# RasPi-BplusHAT.net
KiCad netlist of a schematic drawn in EAGLE
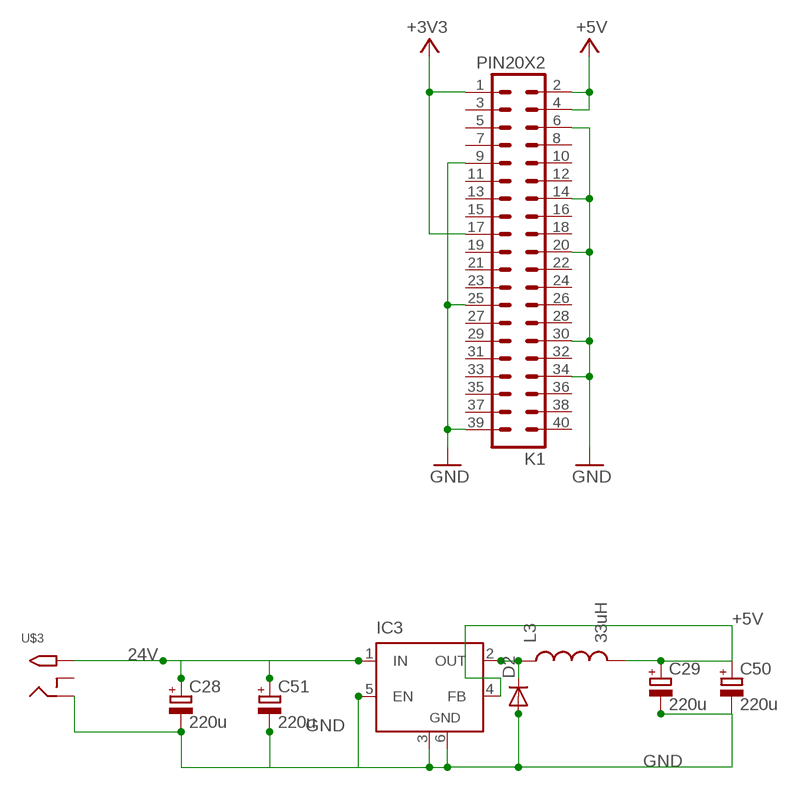
[diagram p0: schematic, sheet 1]
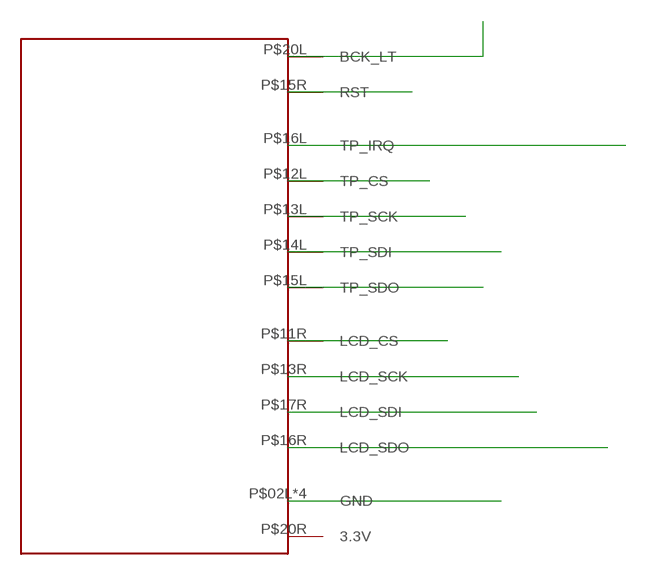
[diagram p1: schematic, sheet 2]

(export (version "E")
  (design (tool "Eeschema 10.0.6"))
  (components
    (comp (ref "C28")
      (value "220u")
      (footprint "eagle-import:E2,5-7")
      (libsource (lib "eagle-import") (part "CPOL-EUE2.5-7"))
    )
    (comp (ref "C29")
      (value "220u")
      (footprint "eagle-import:E2,5-7")
      (libsource (lib "eagle-import") (part "CPOL-EUE2.5-7"))
    )
    (comp (ref "C50")
      (value "220u")
      (footprint "eagle-import:PANASONIC_D")
      (libsource (lib "eagle-import") (part "CPOL-EUD"))
    )
    (comp (ref "C51")
      (value "220u")
      (footprint "eagle-import:PANASONIC_D")
      (libsource (lib "eagle-import") (part "CPOL-EUD"))
    )
    (comp (ref "D2")
      (value "DIODE-DO-214AC")
      (footprint "eagle-import:DO-214AC")
      (libsource (lib "eagle-import") (part "DIODE-DO-214AC"))
    )
    (comp (ref "IC3")
      (value "LM2596S")
      (footprint "eagle-import:TO263-5")
      (libsource (lib "eagle-import") (part "LM2596S"))
    )
    (comp (ref "K1")
      (value "PIN20X2")
      (footprint "eagle-import:PIN_20X2")
      (libsource (lib "eagle-import") (part "PIN20X2"))
    )
    (comp (ref "L3")
      (value "33uH")
      (footprint "eagle-import:CDRH125")
      (libsource (lib "eagle-import") (part "INDUCTORPWR"))
    )
    (comp (ref "U$3")
      (value "2.1MMJACKTHM")
      (footprint "eagle-import:PJ-102A")
      (libsource (lib "eagle-import") (part "2.1MMJACKTHM"))
    )
    (comp (ref "U$1")
      (value "HY28BSTD")
      (footprint "eagle-import:HY28B")
      (libsource (lib "eagle-import") (part "HY28BSTD"))
    )
  )
  (nets
    (net (code "1") (name "+3V3") (class "Default")
      (node (ref "K1") (pin "1") (pinfunction "1_1") (pintype "passive"))
      (node (ref "K1") (pin "17") (pinfunction "17_17") (pintype "passive"))
    )
    (net (code "2") (name "+5V") (class "Default")
      (node (ref "C29") (pin "+") (pinfunction "+_+") (pintype "passive"))
      (node (ref "C50") (pin "+") (pinfunction "+_+") (pintype "passive"))
      (node (ref "IC3") (pin "4") (pinfunction "FB_4") (pintype "input"))
      (node (ref "K1") (pin "2") (pinfunction "2_2") (pintype "passive"))
      (node (ref "K1") (pin "4") (pinfunction "4_4") (pintype "passive"))
      (node (ref "L3") (pin "2") (pinfunction "2_2") (pintype "passive"))
    )
    (net (code "3") (name "24V") (class "Default")
      (node (ref "C28") (pin "+") (pinfunction "+_+") (pintype "passive"))
      (node (ref "C51") (pin "+") (pinfunction "+_+") (pintype "passive"))
      (node (ref "IC3") (pin "1") (pinfunction "IN_1") (pintype "input"))
      (node (ref "U$3") (pin "TIP") (pinfunction "TIP_TIP") (pintype "bidirectional"))
    )
    (net (code "4") (name "GND") (class "Default")
      (node (ref "C28") (pin "-") (pinfunction "-_-") (pintype "passive"))
      (node (ref "C29") (pin "-") (pinfunction "-_-") (pintype "passive"))
      (node (ref "C50") (pin "-") (pinfunction "-_-") (pintype "passive"))
      (node (ref "C51") (pin "-") (pinfunction "-_-") (pintype "passive"))
      (node (ref "D2") (pin "2") (pinfunction "A_2") (pintype "passive"))
      (node (ref "IC3") (pin "3") (pinfunction "GND_3") (pintype "power_in"))
      (node (ref "IC3") (pin "5") (pinfunction "EN_5") (pintype "input"))
      (node (ref "IC3") (pin "6") (pinfunction "GND_6") (pintype "power_in"))
      (node (ref "K1") (pin "14") (pinfunction "14_14") (pintype "passive"))
      (node (ref "K1") (pin "20") (pinfunction "20_20") (pintype "passive"))
      (node (ref "K1") (pin "25") (pinfunction "25_25") (pintype "passive"))
      (node (ref "K1") (pin "30") (pinfunction "30_30") (pintype "passive"))
      (node (ref "K1") (pin "34") (pinfunction "34_34") (pintype "passive"))
      (node (ref "K1") (pin "39") (pinfunction "39_39") (pintype "passive"))
      (node (ref "K1") (pin "6") (pinfunction "6_6") (pintype "passive"))
      (node (ref "K1") (pin "9") (pinfunction "9_9") (pintype "passive"))
      (node (ref "U$3") (pin "RING") (pinfunction "RING_RING") (pintype "bidirectional"))
    )
    (net (code "5") (name "Net-(D2-C)") (class "Default")
      (node (ref "D2") (pin "1") (pinfunction "C_1") (pintype "passive"))
      (node (ref "IC3") (pin "2") (pinfunction "OUT_2") (pintype "output"))
      (node (ref "L3") (pin "1") (pinfunction "1_1") (pintype "passive"))
    )
    (net (code "6") (name "Net-(U$1-GND-PadP$02L)") (class "Default")
      (node (ref "U$1") (pin "P$02L") (pinfunction "GND_P$02L") (pintype "bidirectional"))
      (node (ref "U$1") (pin "P$02R") (pinfunction "GND_P$02R") (pintype "bidirectional"))
      (node (ref "U$1") (pin "P$19L") (pinfunction "GND_P$19L") (pintype "bidirectional"))
      (node (ref "U$1") (pin "P$19R") (pinfunction "GND_P$19R") (pintype "bidirectional"))
    )
    (net (code "7") (name "unconnected-(K1-Pad3)") (class "Default")
      (node (ref "K1") (pin "3") (pinfunction "3_3") (pintype "passive"))
    )
    (net (code "8") (name "unconnected-(K1-Pad5)") (class "Default")
      (node (ref "K1") (pin "5") (pinfunction "5_5") (pintype "passive"))
    )
    (net (code "9") (name "unconnected-(K1-Pad7)") (class "Default")
      (node (ref "K1") (pin "7") (pinfunction "7_7") (pintype "passive"))
    )
    (net (code "10") (name "unconnected-(K1-Pad8)") (class "Default")
      (node (ref "K1") (pin "8") (pinfunction "8_8") (pintype "passive"))
    )
    (net (code "11") (name "unconnected-(K1-Pad10)") (class "Default")
      (node (ref "K1") (pin "10") (pinfunction "10_10") (pintype "passive"))
    )
    (net (code "12") (name "unconnected-(K1-Pad11)") (class "Default")
      (node (ref "K1") (pin "11") (pinfunction "11_11") (pintype "passive"))
    )
    (net (code "13") (name "unconnected-(K1-Pad12)") (class "Default")
      (node (ref "K1") (pin "12") (pinfunction "12_12") (pintype "passive"))
    )
    (net (code "14") (name "unconnected-(K1-Pad13)") (class "Default")
      (node (ref "K1") (pin "13") (pinfunction "13_13") (pintype "passive"))
    )
    (net (code "15") (name "unconnected-(K1-Pad15)") (class "Default")
      (node (ref "K1") (pin "15") (pinfunction "15_15") (pintype "passive"))
    )
    (net (code "16") (name "unconnected-(K1-Pad16)") (class "Default")
      (node (ref "K1") (pin "16") (pinfunction "16_16") (pintype "passive"))
    )
    (net (code "17") (name "unconnected-(K1-Pad18)") (class "Default")
      (node (ref "K1") (pin "18") (pinfunction "18_18") (pintype "passive"))
    )
    (net (code "18") (name "unconnected-(K1-Pad19)") (class "Default")
      (node (ref "K1") (pin "19") (pinfunction "19_19") (pintype "passive"))
    )
    (net (code "19") (name "unconnected-(K1-Pad21)") (class "Default")
      (node (ref "K1") (pin "21") (pinfunction "21_21") (pintype "passive"))
    )
    (net (code "20") (name "unconnected-(K1-Pad22)") (class "Default")
      (node (ref "K1") (pin "22") (pinfunction "22_22") (pintype "passive"))
    )
    (net (code "21") (name "unconnected-(K1-Pad23)") (class "Default")
      (node (ref "K1") (pin "23") (pinfunction "23_23") (pintype "passive"))
    )
    (net (code "22") (name "unconnected-(K1-Pad24)") (class "Default")
      (node (ref "K1") (pin "24") (pinfunction "24_24") (pintype "passive"))
    )
    (net (code "23") (name "unconnected-(K1-Pad26)") (class "Default")
      (node (ref "K1") (pin "26") (pinfunction "26_26") (pintype "passive"))
    )
    (net (code "24") (name "unconnected-(K1-Pad27)") (class "Default")
      (node (ref "K1") (pin "27") (pinfunction "27_27") (pintype "passive"))
    )
    (net (code "25") (name "unconnected-(K1-Pad28)") (class "Default")
      (node (ref "K1") (pin "28") (pinfunction "28_28") (pintype "passive"))
    )
    (net (code "26") (name "unconnected-(K1-Pad29)") (class "Default")
      (node (ref "K1") (pin "29") (pinfunction "29_29") (pintype "passive"))
    )
    (net (code "27") (name "unconnected-(K1-Pad31)") (class "Default")
      (node (ref "K1") (pin "31") (pinfunction "31_31") (pintype "passive"))
    )
    (net (code "28") (name "unconnected-(K1-Pad32)") (class "Default")
      (node (ref "K1") (pin "32") (pinfunction "32_32") (pintype "passive"))
    )
    (net (code "29") (name "unconnected-(K1-Pad33)") (class "Default")
      (node (ref "K1") (pin "33") (pinfunction "33_33") (pintype "passive"))
    )
    (net (code "30") (name "unconnected-(K1-Pad35)") (class "Default")
      (node (ref "K1") (pin "35") (pinfunction "35_35") (pintype "passive"))
    )
    (net (code "31") (name "unconnected-(K1-Pad36)") (class "Default")
      (node (ref "K1") (pin "36") (pinfunction "36_36") (pintype "passive"))
    )
    (net (code "32") (name "unconnected-(K1-Pad37)") (class "Default")
      (node (ref "K1") (pin "37") (pinfunction "37_37") (pintype "passive"))
    )
    (net (code "33") (name "unconnected-(K1-Pad38)") (class "Default")
      (node (ref "K1") (pin "38") (pinfunction "38_38") (pintype "passive"))
    )
    (net (code "34") (name "unconnected-(K1-Pad40)") (class "Default")
      (node (ref "K1") (pin "40") (pinfunction "40_40") (pintype "passive"))
    )
    (net (code "35") (name "unconnected-(U$1-3.3V-PadP$20R)") (class "Default")
      (node (ref "U$1") (pin "P$20R") (pinfunction "3.3V_P$20R") (pintype "bidirectional"))
    )
    (net (code "36") (name "unconnected-(U$1-BCK_LT-PadP$20L)") (class "Default")
      (node (ref "U$1") (pin "P$20L") (pinfunction "BCK_LT_P$20L") (pintype "bidirectional"))
    )
    (net (code "37") (name "unconnected-(U$1-LCD_CS-PadP$11R)") (class "Default")
      (node (ref "U$1") (pin "P$11R") (pinfunction "LCD_CS_P$11R") (pintype "bidirectional"))
    )
    (net (code "38") (name "unconnected-(U$1-LCD_SCK-PadP$13R)") (class "Default")
      (node (ref "U$1") (pin "P$13R") (pinfunction "LCD_SCK_P$13R") (pintype "bidirectional"))
    )
    (net (code "39") (name "unconnected-(U$1-LCD_SDI-PadP$17R)") (class "Default")
      (node (ref "U$1") (pin "P$17R") (pinfunction "LCD_SDI_P$17R") (pintype "bidirectional"))
    )
    (net (code "40") (name "unconnected-(U$1-LCD_SDO-PadP$16R)") (class "Default")
      (node (ref "U$1") (pin "P$16R") (pinfunction "LCD_SDO_P$16R") (pintype "bidirectional"))
    )
    (net (code "41") (name "unconnected-(U$1-RST-PadP$15R)") (class "Default")
      (node (ref "U$1") (pin "P$15R") (pinfunction "RST_P$15R") (pintype "bidirectional"))
    )
    (net (code "42") (name "unconnected-(U$1-TP_CS-PadP$12L)") (class "Default")
      (node (ref "U$1") (pin "P$12L") (pinfunction "TP_CS_P$12L") (pintype "bidirectional"))
    )
    (net (code "43") (name "unconnected-(U$1-TP_IRQ-PadP$16L)") (class "Default")
      (node (ref "U$1") (pin "P$16L") (pinfunction "TP_IRQ_P$16L") (pintype "bidirectional"))
    )
    (net (code "44") (name "unconnected-(U$1-TP_SCK-PadP$13L)") (class "Default")
      (node (ref "U$1") (pin "P$13L") (pinfunction "TP_SCK_P$13L") (pintype "bidirectional"))
    )
    (net (code "45") (name "unconnected-(U$1-TP_SDI-PadP$14L)") (class "Default")
      (node (ref "U$1") (pin "P$14L") (pinfunction "TP_SDI_P$14L") (pintype "bidirectional"))
    )
    (net (code "46") (name "unconnected-(U$1-TP_SDO-PadP$15L)") (class "Default")
      (node (ref "U$1") (pin "P$15L") (pinfunction "TP_SDO_P$15L") (pintype "bidirectional"))
    )
    (net (code "47") (name "unconnected-(U$3-PadRING_SW)") (class "Default")
      (node (ref "U$3") (pin "RING_SW") (pinfunction "RING_SW_RING_SW") (pintype "bidirectional"))
    )
  )
)
